# Sheet1.net
KiCad netlist of a schematic drawn in Altium Designer
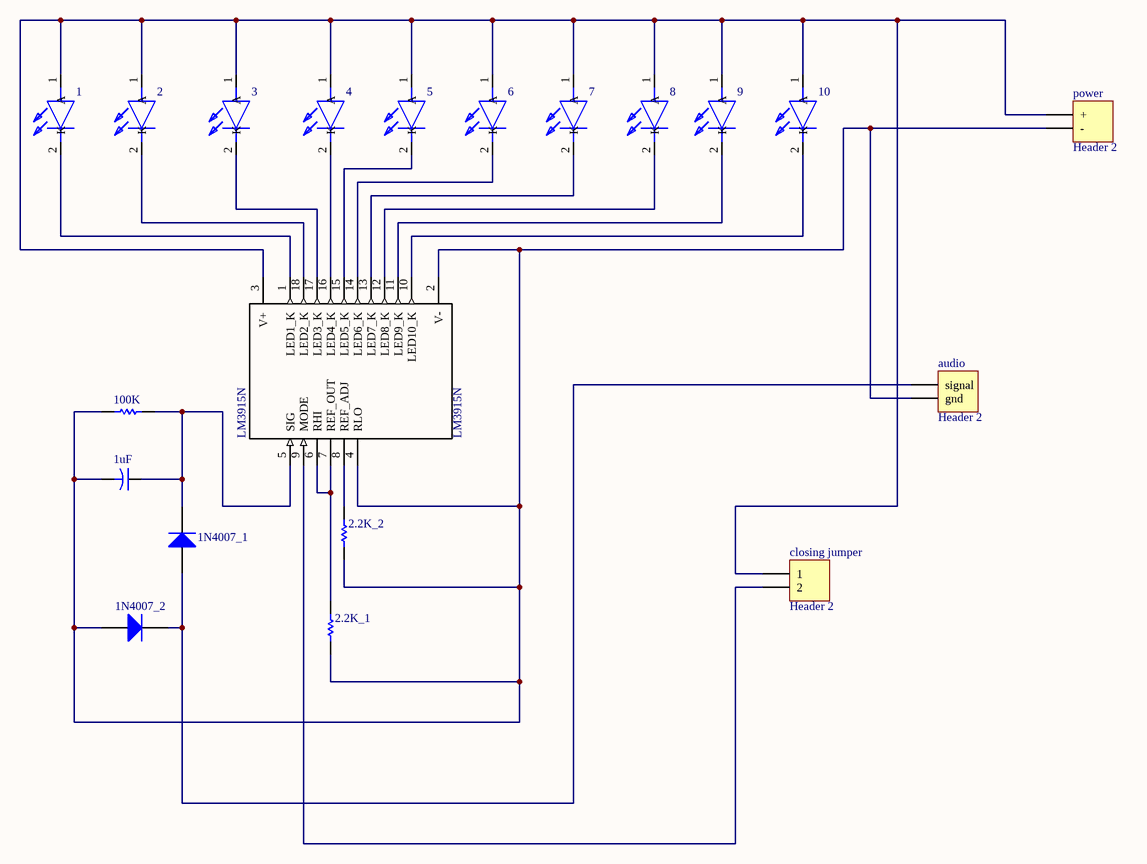
[diagram p0: Sheet1.SchDoc]

(export (version "E")
  (design (tool "Eeschema 10.0.6"))
  (components
    (comp (ref "1")
      (value "L-53GD")
      (footprint "SamacSys:L-53GD")
      (description "LED")
      (fields (field (name "RS PART NUMBER") "2286004A"))
      (libsource (lib "SamacSys") (part "L-53GD"))
    )
    (comp (ref "1N4007_1")
      (value "1N4007")
      (footprint "DO-41")
      (description "1 Amp General Purpose Rectifier")
      (fields (field (name "PUBLISHER") "Altium Limited"))
      (libsource (lib "Miscellaneous Devices") (part "Diode 1N4007"))
    )
    (comp (ref "1N4007_2")
      (value "Diode 1N4007")
      (footprint "DO-41")
      (description "1 Amp General Purpose Rectifier")
      (fields (field (name "PUBLISHER") "Altium Limited"))
      (libsource (lib "Miscellaneous Devices") (part "Diode 1N4007"))
    )
    (comp (ref "1uF")
      (value "Cap2")
      (footprint "CAPR5-4X5")
      (description "Capacitor")
      (fields (field (name "PUBLISHER") "Altium Limited"))
      (libsource (lib "Miscellaneous Devices") (part "Cap2"))
    )
    (comp (ref "2")
      (value "L-53GD")
      (footprint "SamacSys:L-53GD")
      (description "LED")
      (fields (field (name "RS PART NUMBER") "2286004A"))
      (libsource (lib "SamacSys") (part "L-53GD"))
    )
    (comp (ref "2.2K_1")
      (value "Res1")
      (footprint "AXIAL-0.3")
      (description "Resistor")
      (fields (field (name "PUBLISHER") "Altium Limited"))
      (libsource (lib "Miscellaneous Devices") (part "Res1"))
    )
    (comp (ref "2.2K_2")
      (value "Res1")
      (footprint "AXIAL-0.3")
      (description "Resistor")
      (fields (field (name "PUBLISHER") "Altium Limited"))
      (libsource (lib "Miscellaneous Devices") (part "Res1"))
    )
    (comp (ref "3")
      (value "L-53GD")
      (footprint "SamacSys:L-53GD")
      (description "LED")
      (fields (field (name "RS PART NUMBER") "2286004A"))
      (libsource (lib "SamacSys") (part "L-53GD"))
    )
    (comp (ref "4")
      (value "L-53GD")
      (footprint "SamacSys:L-53GD")
      (description "LED")
      (fields (field (name "RS PART NUMBER") "2286004A"))
      (libsource (lib "SamacSys") (part "L-53GD"))
    )
    (comp (ref "5")
      (value "L-53GD")
      (footprint "SamacSys:L-53GD")
      (description "LED")
      (fields (field (name "RS PART NUMBER") "2286004A"))
      (libsource (lib "SamacSys") (part "L-53GD"))
    )
    (comp (ref "6")
      (value "L-53GD")
      (footprint "SamacSys:L-53GD")
      (description "LED")
      (fields (field (name "RS PART NUMBER") "2286004A"))
      (libsource (lib "SamacSys") (part "L-53GD"))
    )
    (comp (ref "7")
      (value "L-53GD")
      (footprint "SamacSys:L-53GD")
      (description "LED")
      (fields (field (name "RS PART NUMBER") "2286004A"))
      (libsource (lib "SamacSys") (part "L-53GD"))
    )
    (comp (ref "8")
      (value "L-53GD")
      (footprint "SamacSys:L-53GD")
      (description "LED")
      (fields (field (name "RS PART NUMBER") "2286004A"))
      (libsource (lib "SamacSys") (part "L-53GD"))
    )
    (comp (ref "9")
      (value "L-53GD")
      (footprint "SamacSys:L-53GD")
      (description "LED")
      (fields (field (name "RS PART NUMBER") "2286004A"))
      (libsource (lib "SamacSys") (part "L-53GD"))
    )
    (comp (ref "10")
      (value "L-53GD")
      (footprint "SamacSys:L-53GD")
      (description "LED")
      (fields (field (name "RS PART NUMBER") "2286004A"))
      (libsource (lib "SamacSys") (part "L-53GD"))
    )
    (comp (ref "100K")
      (value "Res1")
      (footprint "AXIAL-0.3")
      (description "Resistor")
      (fields (field (name "PUBLISHER") "Altium Limited"))
      (libsource (lib "Miscellaneous Devices") (part "Res1"))
    )
    (comp (ref "audio")
      (value "Header 2")
      (footprint "HDR1X2")
      (description "Header, 2-Pin")
      (fields (field (name "PUBLISHER") "Altium Limited"))
      (libsource (lib "Miscellaneous Connectors") (part "Header 2"))
    )
    (comp (ref "closing jumper")
      (value "Header 2")
      (footprint "HDR1X2")
      (description "Header, 2-Pin")
      (fields (field (name "PUBLISHER") "Altium Limited"))
      (libsource (lib "Miscellaneous Connectors") (part "Header 2"))
    )
    (comp (ref "LM3915N")
      (value "LM3915N")
      (footprint "*DIP795W25P254L2337H533Q18B")
      (description "LED DRVR 10Segment 3.3V/5V/9V/12V/15V/18V/24V 18-Pin PDIP Tube")
      (fields (field (name "MF") "Texas Instruments") (field (name "MP") "LM3915N-1"))
      (libsource (lib "LM3915N-1") (part "LM3915N-1"))
    )
    (comp (ref "power")
      (value "Header 2")
      (footprint "HDR1X2")
      (description "Header, 2-Pin")
      (fields (field (name "PUBLISHER") "Altium Limited"))
      (libsource (lib "Miscellaneous Connectors") (part "Header 2"))
    )
  )
  (nets
    (net (code "1") (name "Net-(1-A)") (class "Default")
      (node (ref "1") (pin "1") (pinfunction "A_1") (pintype "passive"))
      (node (ref "10") (pin "1") (pinfunction "A_1") (pintype "passive"))
      (node (ref "2") (pin "1") (pinfunction "A_1") (pintype "passive"))
      (node (ref "3") (pin "1") (pinfunction "A_1") (pintype "passive"))
      (node (ref "4") (pin "1") (pinfunction "A_1") (pintype "passive"))
      (node (ref "5") (pin "1") (pinfunction "A_1") (pintype "passive"))
      (node (ref "6") (pin "1") (pinfunction "A_1") (pintype "passive"))
      (node (ref "7") (pin "1") (pinfunction "A_1") (pintype "passive"))
      (node (ref "8") (pin "1") (pinfunction "A_1") (pintype "passive"))
      (node (ref "9") (pin "1") (pinfunction "A_1") (pintype "passive"))
      (node (ref "LM3915N") (pin "3") (pinfunction "V+_3") (pintype "power_in"))
      (node (ref "closing jumper") (pin "1") (pinfunction "1_1") (pintype "passive"))
      (node (ref "power") (pin "1") (pinfunction "1_1") (pintype "passive"))
    )
    (net (code "2") (name "Net-(1-K)") (class "Default")
      (node (ref "1") (pin "2") (pinfunction "K_2") (pintype "passive"))
      (node (ref "LM3915N") (pin "1") (pinfunction "LED1_K_1") (pintype "output"))
    )
    (net (code "3") (name "Net-(1N4007_1-A)") (class "Default")
      (node (ref "1N4007_1") (pin "1") (pinfunction "A_1") (pintype "passive"))
      (node (ref "1N4007_2") (pin "2") (pinfunction "K_2") (pintype "passive"))
      (node (ref "audio") (pin "1") (pinfunction "1_1") (pintype "passive"))
    )
    (net (code "4") (name "Net-(1N4007_1-K)") (class "Default")
      (node (ref "100K") (pin "2") (pinfunction "2_2") (pintype "passive"))
      (node (ref "1N4007_1") (pin "2") (pinfunction "K_2") (pintype "passive"))
      (node (ref "1uF") (pin "1") (pinfunction "1_1") (pintype "passive"))
      (node (ref "LM3915N") (pin "5") (pinfunction "SIG_5") (pintype "input"))
    )
    (net (code "5") (name "Net-(1N4007_2-A)") (class "Default")
      (node (ref "100K") (pin "1") (pinfunction "1_1") (pintype "passive"))
      (node (ref "1N4007_2") (pin "1") (pinfunction "A_1") (pintype "passive"))
      (node (ref "1uF") (pin "2") (pinfunction "2_2") (pintype "passive"))
      (node (ref "2.2K_1") (pin "1") (pinfunction "1_1") (pintype "passive"))
      (node (ref "2.2K_2") (pin "1") (pinfunction "1_1") (pintype "passive"))
      (node (ref "LM3915N") (pin "2") (pinfunction "V-_2") (pintype "power_in"))
      (node (ref "LM3915N") (pin "4") (pinfunction "RLO_4") (pintype "passive"))
      (node (ref "audio") (pin "2") (pinfunction "2_2") (pintype "passive"))
      (node (ref "power") (pin "2") (pinfunction "2_2") (pintype "passive"))
    )
    (net (code "6") (name "Net-(2-K)") (class "Default")
      (node (ref "2") (pin "2") (pinfunction "K_2") (pintype "passive"))
      (node (ref "LM3915N") (pin "18") (pinfunction "LED2_K_18") (pintype "output"))
    )
    (net (code "7") (name "Net-(3-K)") (class "Default")
      (node (ref "3") (pin "2") (pinfunction "K_2") (pintype "passive"))
      (node (ref "LM3915N") (pin "17") (pinfunction "LED3_K_17") (pintype "output"))
    )
    (net (code "8") (name "Net-(4-K)") (class "Default")
      (node (ref "4") (pin "2") (pinfunction "K_2") (pintype "passive"))
      (node (ref "LM3915N") (pin "16") (pinfunction "LED4_K_16") (pintype "output"))
    )
    (net (code "9") (name "Net-(5-K)") (class "Default")
      (node (ref "5") (pin "2") (pinfunction "K_2") (pintype "passive"))
      (node (ref "LM3915N") (pin "15") (pinfunction "LED5_K_15") (pintype "output"))
    )
    (net (code "10") (name "Net-(6-K)") (class "Default")
      (node (ref "6") (pin "2") (pinfunction "K_2") (pintype "passive"))
      (node (ref "LM3915N") (pin "14") (pinfunction "LED6_K_14") (pintype "output"))
    )
    (net (code "11") (name "Net-(7-K)") (class "Default")
      (node (ref "7") (pin "2") (pinfunction "K_2") (pintype "passive"))
      (node (ref "LM3915N") (pin "13") (pinfunction "LED7_K_13") (pintype "output"))
    )
    (net (code "12") (name "Net-(8-K)") (class "Default")
      (node (ref "8") (pin "2") (pinfunction "K_2") (pintype "passive"))
      (node (ref "LM3915N") (pin "12") (pinfunction "LED8_K_12") (pintype "output"))
    )
    (net (code "13") (name "Net-(9-K)") (class "Default")
      (node (ref "9") (pin "2") (pinfunction "K_2") (pintype "passive"))
      (node (ref "LM3915N") (pin "11") (pinfunction "LED9_K_11") (pintype "output"))
    )
    (net (code "14") (name "Net-(10-K)") (class "Default")
      (node (ref "10") (pin "2") (pinfunction "K_2") (pintype "passive"))
      (node (ref "LM3915N") (pin "10") (pinfunction "LED10_K_10") (pintype "output"))
    )
    (net (code "15") (name "Net-(LM3915N-MODE)") (class "Default")
      (node (ref "LM3915N") (pin "9") (pinfunction "MODE_9") (pintype "input"))
      (node (ref "closing jumper") (pin "2") (pinfunction "2_2") (pintype "passive"))
    )
    (net (code "16") (name "Net-(LM3915N-REF_ADJ)") (class "Default")
      (node (ref "2.2K_2") (pin "2") (pinfunction "2_2") (pintype "passive"))
      (node (ref "LM3915N") (pin "8") (pinfunction "REF_ADJ_8") (pintype "passive"))
    )
    (net (code "17") (name "Net-(LM3915N-REF_OUT)") (class "Default")
      (node (ref "2.2K_1") (pin "2") (pinfunction "2_2") (pintype "passive"))
      (node (ref "LM3915N") (pin "6") (pinfunction "RHI_6") (pintype "passive"))
      (node (ref "LM3915N") (pin "7") (pinfunction "REF_OUT_7") (pintype "passive"))
    )
  )
)
